# Power_Supply-V_1_0_0_0.net
KiCad netlist of a schematic drawn in EAGLE
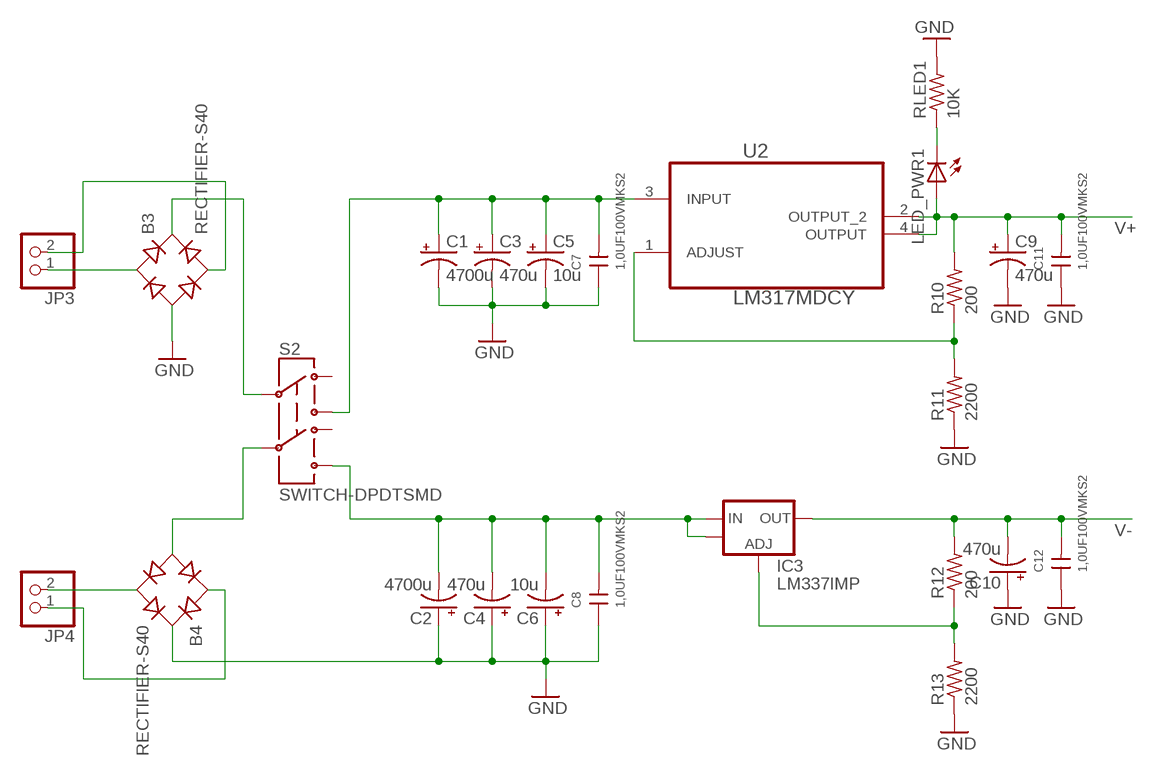
[diagram p0: schematic, sheet 1]

(export (version "E")
  (design (tool "Eeschema 10.0.6"))
  (components
    (comp (ref "B3")
      (value "RECTIFIER-S40")
      (footprint "eagle-import:TO-269AA")
      (libsource (lib "eagle-import") (part "RECTIFIER-S40"))
    )
    (comp (ref "B4")
      (value "RECTIFIER-S40")
      (footprint "eagle-import:TO-269AA")
      (libsource (lib "eagle-import") (part "RECTIFIER-S40"))
    )
    (comp (ref "C1")
      (value "4700u")
      (footprint "eagle-import:E7,5-16")
      (libsource (lib "eagle-import") (part "CPOL-USE7.5-16"))
    )
    (comp (ref "C2")
      (value "4700u")
      (footprint "eagle-import:E7,5-16")
      (libsource (lib "eagle-import") (part "CPOL-USE7.5-16"))
    )
    (comp (ref "C3")
      (value "470u")
      (footprint "eagle-import:E3,5-8")
      (libsource (lib "eagle-import") (part "CPOL-USE3.5-8"))
    )
    (comp (ref "C4")
      (value "470u")
      (footprint "eagle-import:E3,5-8")
      (libsource (lib "eagle-import") (part "CPOL-USE3.5-8"))
    )
    (comp (ref "C5")
      (value "10u")
      (footprint "eagle-import:E2-5")
      (libsource (lib "eagle-import") (part "CPOL-USE2-5"))
    )
    (comp (ref "C6")
      (value "10u")
      (footprint "eagle-import:E2-5")
      (libsource (lib "eagle-import") (part "CPOL-USE2-5"))
    )
    (comp (ref "C7")
      (value "1,0UF100VMKS2")
      (footprint "eagle-import:7,2X13,0RM5,0")
      (libsource (lib "eagle-import") (part "1,0UF100VMKS2"))
    )
    (comp (ref "C8")
      (value "1,0UF100VMKS2")
      (footprint "eagle-import:7,2X13,0RM5,0")
      (libsource (lib "eagle-import") (part "1,0UF100VMKS2"))
    )
    (comp (ref "C9")
      (value "470u")
      (footprint "eagle-import:E3,5-8")
      (libsource (lib "eagle-import") (part "CPOL-USE3.5-8"))
    )
    (comp (ref "C10")
      (value "470u")
      (footprint "eagle-import:E3,5-8")
      (libsource (lib "eagle-import") (part "CPOL-USE3.5-8"))
    )
    (comp (ref "C11")
      (value "1,0UF100VMKS2")
      (footprint "eagle-import:7,2X13,0RM5,0")
      (libsource (lib "eagle-import") (part "1,0UF100VMKS2"))
    )
    (comp (ref "C12")
      (value "1,0UF100VMKS2")
      (footprint "eagle-import:7,2X13,0RM5,0")
      (libsource (lib "eagle-import") (part "1,0UF100VMKS2"))
    )
    (comp (ref "IC3")
      (value "LM337IMP")
      (footprint "eagle-import:SOT-223")
      (libsource (lib "eagle-import") (part "LM337IMP"))
    )
    (comp (ref "JP3")
      (value "PINHD-1X2")
      (footprint "eagle-import:1X02")
      (libsource (lib "eagle-import") (part "PINHD-1X2"))
    )
    (comp (ref "JP4")
      (value "PINHD-1X2")
      (footprint "eagle-import:1X02")
      (libsource (lib "eagle-import") (part "PINHD-1X2"))
    )
    (comp (ref "LED_PWR1")
      (value "LEDCHIP-LED0603")
      (footprint "eagle-import:CHIP-LED0603")
      (libsource (lib "eagle-import") (part "LEDCHIP-LED0603"))
    )
    (comp (ref "R10")
      (value "200")
      (footprint "eagle-import:R0603")
      (libsource (lib "eagle-import") (part "R-US_R0603"))
    )
    (comp (ref "R11")
      (value "2200")
      (footprint "eagle-import:R0603")
      (libsource (lib "eagle-import") (part "R-US_R0603"))
    )
    (comp (ref "R12")
      (value "200")
      (footprint "eagle-import:R0603")
      (libsource (lib "eagle-import") (part "R-US_R0603"))
    )
    (comp (ref "R13")
      (value "2200")
      (footprint "eagle-import:R0603")
      (libsource (lib "eagle-import") (part "R-US_R0603"))
    )
    (comp (ref "RLED1")
      (value "10K")
      (footprint "eagle-import:R0603")
      (libsource (lib "eagle-import") (part "R-US_R0603"))
    )
    (comp (ref "S2")
      (value "SWITCH-DPDTSMD")
      (footprint "eagle-import:AYZ0202")
      (libsource (lib "eagle-import") (part "SWITCH-DPDTSMD"))
    )
    (comp (ref "U2")
      (value "LM317MDCY")
      (footprint "eagle-import:SOT230P700X180-4N")
      (libsource (lib "eagle-import") (part "LM317MDCY"))
    )
  )
  (nets
    (net (code "1") (name "/V+") (class "Default")
      (node (ref "C11") (pin "2") (pinfunction "2_2") (pintype "passive"))
      (node (ref "C9") (pin "+") (pinfunction "+_+") (pintype "passive"))
      (node (ref "LED_PWR1") (pin "A") (pinfunction "A_A") (pintype "passive"))
      (node (ref "R10") (pin "2") (pinfunction "2_2") (pintype "passive"))
      (node (ref "U2") (pin "2") (pinfunction "OUTPUT_2_2") (pintype "output"))
      (node (ref "U2") (pin "4") (pinfunction "OUTPUT_4") (pintype "output"))
    )
    (net (code "2") (name "/V-") (class "Default")
      (node (ref "C10") (pin "-") (pinfunction "-_-") (pintype "passive"))
      (node (ref "C12") (pin "2") (pinfunction "2_2") (pintype "passive"))
      (node (ref "IC3") (pin "3") (pinfunction "OUT_3") (pintype "passive"))
      (node (ref "R12") (pin "2") (pinfunction "2_2") (pintype "passive"))
    )
    (net (code "3") (name "GND") (class "Default")
      (node (ref "B3") (pin "-") (pinfunction "-_-") (pintype "passive"))
      (node (ref "B4") (pin "+") (pinfunction "+_+") (pintype "passive"))
      (node (ref "C1") (pin "-") (pinfunction "-_-") (pintype "passive"))
      (node (ref "C10") (pin "+") (pinfunction "+_+") (pintype "passive"))
      (node (ref "C11") (pin "1") (pinfunction "1_1") (pintype "passive"))
      (node (ref "C12") (pin "1") (pinfunction "1_1") (pintype "passive"))
      (node (ref "C2") (pin "+") (pinfunction "+_+") (pintype "passive"))
      (node (ref "C3") (pin "-") (pinfunction "-_-") (pintype "passive"))
      (node (ref "C4") (pin "+") (pinfunction "+_+") (pintype "passive"))
      (node (ref "C5") (pin "-") (pinfunction "-_-") (pintype "passive"))
      (node (ref "C6") (pin "+") (pinfunction "+_+") (pintype "passive"))
      (node (ref "C7") (pin "1") (pinfunction "1_1") (pintype "passive"))
      (node (ref "C8") (pin "1") (pinfunction "1_1") (pintype "passive"))
      (node (ref "C9") (pin "-") (pinfunction "-_-") (pintype "passive"))
      (node (ref "R11") (pin "1") (pinfunction "1_1") (pintype "passive"))
      (node (ref "R13") (pin "1") (pinfunction "1_1") (pintype "passive"))
      (node (ref "RLED1") (pin "2") (pinfunction "2_2") (pintype "passive"))
    )
    (net (code "4") (name "Net-(B3-Pad+)") (class "Default")
      (node (ref "B3") (pin "+") (pinfunction "+_+") (pintype "passive"))
      (node (ref "S2") (pin "2") (pinfunction "2_2") (pintype "bidirectional"))
    )
    (net (code "5") (name "Net-(B3-PadAC1)") (class "Default")
      (node (ref "B3") (pin "AC1") (pinfunction "AC1_AC1") (pintype "passive"))
      (node (ref "JP3") (pin "1") (pinfunction "1_1") (pintype "passive"))
    )
    (net (code "6") (name "Net-(B3-PadAC2)") (class "Default")
      (node (ref "B3") (pin "AC2") (pinfunction "AC2_AC2") (pintype "passive"))
      (node (ref "JP3") (pin "2") (pinfunction "2_2") (pintype "passive"))
    )
    (net (code "7") (name "Net-(B4-Pad-)") (class "Default")
      (node (ref "B4") (pin "-") (pinfunction "-_-") (pintype "passive"))
      (node (ref "S2") (pin "5") (pinfunction "5_5") (pintype "bidirectional"))
    )
    (net (code "8") (name "Net-(B4-PadAC1)") (class "Default")
      (node (ref "B4") (pin "AC1") (pinfunction "AC1_AC1") (pintype "passive"))
      (node (ref "JP4") (pin "1") (pinfunction "1_1") (pintype "passive"))
    )
    (net (code "9") (name "Net-(B4-PadAC2)") (class "Default")
      (node (ref "B4") (pin "AC2") (pinfunction "AC2_AC2") (pintype "passive"))
      (node (ref "JP4") (pin "2") (pinfunction "2_2") (pintype "passive"))
    )
    (net (code "10") (name "Net-(IC3-ADJ)") (class "Default")
      (node (ref "IC3") (pin "1") (pinfunction "ADJ_1") (pintype "input"))
      (node (ref "R12") (pin "1") (pinfunction "1_1") (pintype "passive"))
      (node (ref "R13") (pin "2") (pinfunction "2_2") (pintype "passive"))
    )
    (net (code "11") (name "Net-(IC3-IN)") (class "Default")
      (node (ref "C2") (pin "-") (pinfunction "-_-") (pintype "passive"))
      (node (ref "C4") (pin "-") (pinfunction "-_-") (pintype "passive"))
      (node (ref "C6") (pin "-") (pinfunction "-_-") (pintype "passive"))
      (node (ref "C8") (pin "2") (pinfunction "2_2") (pintype "passive"))
      (node (ref "IC3") (pin "2") (pinfunction "IN_2") (pintype "input"))
      (node (ref "IC3") (pin "4") (pinfunction "P$1_4") (pintype "bidirectional"))
      (node (ref "S2") (pin "6") (pinfunction "6_6") (pintype "bidirectional"))
    )
    (net (code "12") (name "Net-(LED_PWR1-PadC)") (class "Default")
      (node (ref "LED_PWR1") (pin "C") (pinfunction "C_C") (pintype "passive"))
      (node (ref "RLED1") (pin "1") (pinfunction "1_1") (pintype "passive"))
    )
    (net (code "13") (name "Net-(U2-ADJUST)") (class "Default")
      (node (ref "R10") (pin "1") (pinfunction "1_1") (pintype "passive"))
      (node (ref "R11") (pin "2") (pinfunction "2_2") (pintype "passive"))
      (node (ref "U2") (pin "1") (pinfunction "ADJUST_1") (pintype "input"))
    )
    (net (code "14") (name "Net-(U2-INPUT)") (class "Default")
      (node (ref "C1") (pin "+") (pinfunction "+_+") (pintype "passive"))
      (node (ref "C3") (pin "+") (pinfunction "+_+") (pintype "passive"))
      (node (ref "C5") (pin "+") (pinfunction "+_+") (pintype "passive"))
      (node (ref "C7") (pin "2") (pinfunction "2_2") (pintype "passive"))
      (node (ref "S2") (pin "3") (pinfunction "3_3") (pintype "bidirectional"))
      (node (ref "U2") (pin "3") (pinfunction "INPUT_3") (pintype "input"))
    )
    (net (code "15") (name "unconnected-(S2-Pad1)") (class "Default")
      (node (ref "S2") (pin "1") (pinfunction "1_1") (pintype "bidirectional"))
    )
    (net (code "16") (name "unconnected-(S2-Pad4)") (class "Default")
      (node (ref "S2") (pin "4") (pinfunction "4_4") (pintype "bidirectional"))
    )
  )
)
